# NeptuneSense_outdoor_station.net
KiCad netlist of a schematic drawn in Altium Designer
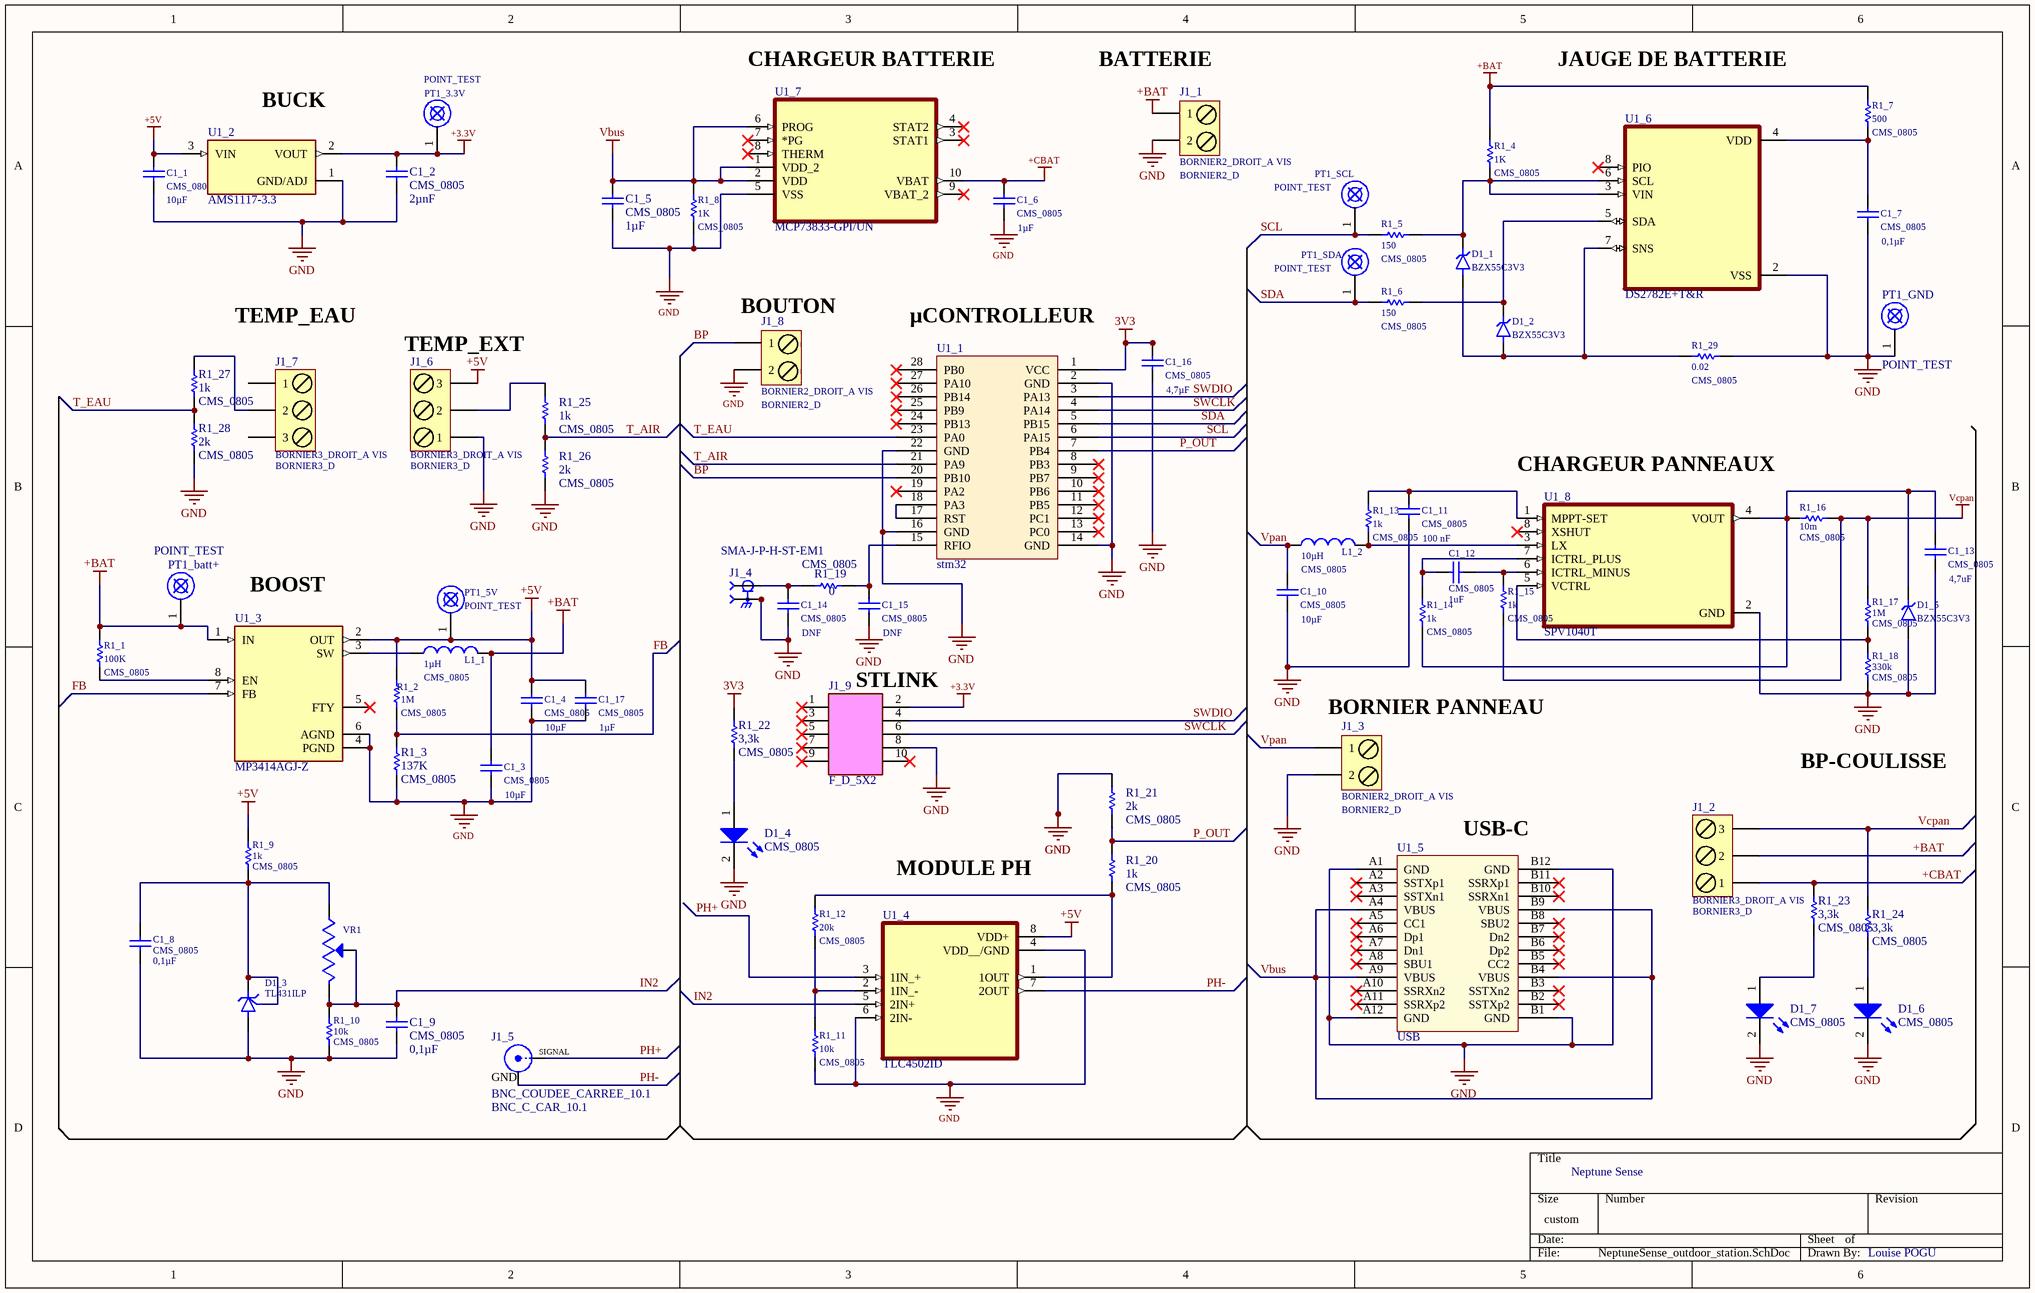
[diagram p0: NeptuneSense_outdoor_station.SchDoc]

(export (version "E")
  (design (tool "Eeschema 10.0.6"))
  (components
    (comp (ref "C1_1")
      (value "10µF")
      (footprint "CONDENSATEUR_CMS_0805")
      (description "CONDENSATEUR CMS CERAMIQUE 0805")
      (fields (field (name "TYPE") "CMS_0805") (field (name "Comment") "CMS_0805"))
      (libsource (lib "composants passifs") (part "CONDENSATEUR_CMS_CER_0805"))
    )
    (comp (ref "C1_2")
      (value "2µnF")
      (footprint "CONDENSATEUR_CMS_0805")
      (description "CONDENSATEUR CMS CERAMIQUE 0805")
      (fields (field (name "TYPE") "CMS_0805") (field (name "Comment") "CMS_0805"))
      (libsource (lib "composants passifs") (part "CONDENSATEUR_CMS_CER_0805"))
    )
    (comp (ref "C1_3")
      (value "10µF")
      (footprint "CONDENSATEUR_CMS_0805")
      (description "CONDENSATEUR CMS CERAMIQUE 0805")
      (fields (field (name "TYPE") "CMS_0805") (field (name "Comment") "CMS_0805"))
      (libsource (lib "composants passifs") (part "CONDENSATEUR_CMS_CER_0805"))
    )
    (comp (ref "C1_4")
      (value "10µF")
      (footprint "CONDENSATEUR_CMS_0805")
      (description "CONDENSATEUR CMS CERAMIQUE 0805")
      (fields (field (name "TYPE") "CMS_0805") (field (name "Comment") "CMS_0805"))
      (libsource (lib "composants passifs") (part "CONDENSATEUR_CMS_CER_0805"))
    )
    (comp (ref "C1_5")
      (value "1µF")
      (footprint "CONDENSATEUR_CMS_0805")
      (description "CONDENSATEUR CMS CERAMIQUE 0805")
      (fields (field (name "TYPE") "CMS_0805") (field (name "Comment") "CMS_0805"))
      (libsource (lib "composants passifs") (part "CONDENSATEUR_CMS_CER_0805"))
    )
    (comp (ref "C1_6")
      (value "1µF")
      (footprint "CONDENSATEUR_CMS_0805")
      (description "CONDENSATEUR CMS CERAMIQUE 0805")
      (fields (field (name "TYPE") "CMS_0805") (field (name "Comment") "CMS_0805"))
      (libsource (lib "composants passifs") (part "CONDENSATEUR_CMS_CER_0805"))
    )
    (comp (ref "C1_7")
      (value "0,1µF")
      (footprint "CONDENSATEUR_CMS_0805")
      (description "CONDENSATEUR CMS CERAMIQUE 0805")
      (fields (field (name "TYPE") "CMS_0805") (field (name "Comment") "CMS_0805"))
      (libsource (lib "composants passifs") (part "CONDENSATEUR_CMS_CER_0805"))
    )
    (comp (ref "C1_8")
      (value "0,1µF")
      (footprint "CONDENSATEUR_CMS_0805")
      (description "CONDENSATEUR CMS CERAMIQUE 0805")
      (fields (field (name "TYPE") "CMS_0805") (field (name "Comment") "CMS_0805"))
      (libsource (lib "composants passifs") (part "CONDENSATEUR_CMS_CER_0805"))
    )
    (comp (ref "C1_9")
      (value "0,1µF")
      (footprint "CONDENSATEUR_CMS_0805")
      (description "CONDENSATEUR CMS CERAMIQUE 0805")
      (fields (field (name "TYPE") "CMS_0805") (field (name "Comment") "CMS_0805"))
      (libsource (lib "composants passifs") (part "CONDENSATEUR_CMS_CER_0805"))
    )
    (comp (ref "C1_10")
      (value "10µF")
      (footprint "CONDENSATEUR_CMS_0805")
      (description "CONDENSATEUR CMS CERAMIQUE 0805")
      (fields (field (name "TYPE") "CMS_0805") (field (name "Comment") "CMS_0805"))
      (libsource (lib "composants passifs") (part "CONDENSATEUR_CMS_CER_0805"))
    )
    (comp (ref "C1_11")
      (value "100 nF")
      (footprint "CONDENSATEUR_CMS_0805")
      (description "CONDENSATEUR CMS CERAMIQUE 0805")
      (fields (field (name "TYPE") "CMS_0805") (field (name "Comment") "CMS_0805"))
      (libsource (lib "composants passifs") (part "CONDENSATEUR_CMS_CER_0805"))
    )
    (comp (ref "C1_12")
      (value "1uF")
      (footprint "CONDENSATEUR_CMS_0805")
      (description "CONDENSATEUR CMS CERAMIQUE 0805")
      (fields (field (name "TYPE") "CMS_0805") (field (name "Comment") "CMS_0805"))
      (libsource (lib "composants passifs") (part "CONDENSATEUR_CMS_CER_0805"))
    )
    (comp (ref "C1_13")
      (value "4,7uF")
      (footprint "CONDENSATEUR_CMS_0805")
      (description "CONDENSATEUR CMS CERAMIQUE 0805")
      (fields (field (name "TYPE") "CMS_0805") (field (name "Comment") "CMS_0805"))
      (libsource (lib "composants passifs") (part "CONDENSATEUR_CMS_CER_0805"))
    )
    (comp (ref "C1_14")
      (value "DNF")
      (footprint "CONDENSATEUR_CMS_0805")
      (description "CONDENSATEUR CMS CERAMIQUE 0805")
      (fields (field (name "TYPE") "CMS_0805") (field (name "Comment") "CMS_0805"))
      (libsource (lib "composants passifs") (part "CONDENSATEUR_CMS_CER_0805"))
    )
    (comp (ref "C1_15")
      (value "DNF")
      (footprint "CONDENSATEUR_CMS_0805")
      (description "CONDENSATEUR CMS CERAMIQUE 0805")
      (fields (field (name "TYPE") "CMS_0805") (field (name "Comment") "CMS_0805"))
      (libsource (lib "composants passifs") (part "CONDENSATEUR_CMS_CER_0805"))
    )
    (comp (ref "C1_16")
      (value "4,7µF")
      (footprint "CONDENSATEUR_CMS_0805")
      (description "CONDENSATEUR CMS CERAMIQUE 0805")
      (fields (field (name "TYPE") "CMS_0805") (field (name "Comment") "CMS_0805"))
      (libsource (lib "composants passifs") (part "CONDENSATEUR_CMS_CER_0805"))
    )
    (comp (ref "C1_17")
      (value "1µF")
      (footprint "CONDENSATEUR_CMS_0805")
      (description "CONDENSATEUR CMS CERAMIQUE 0805")
      (fields (field (name "TYPE") "CMS_0805") (field (name "Comment") "CMS_0805"))
      (libsource (lib "composants passifs") (part "CONDENSATEUR_CMS_CER_0805"))
    )
    (comp (ref "D1_1")
      (value "BZX55C3V3")
      (footprint "DIOAD928W47L399D179")
      (description "Zener Diode Single 3.3V 5% 85Ohm 500mW 2-Pin DO-35 T/R")
      (fields (field (name "MF") "Taiwan Semiconductor"))
      (libsource (lib "ESEO (Ecole Supérieure d'Electronique de l'Ouest)") (part "BZX55C3V3"))
    )
    (comp (ref "D1_2")
      (value "BZX55C3V3")
      (footprint "DIOAD928W47L399D179")
      (description "Zener Diode Single 3.3V 5% 85Ohm 500mW 2-Pin DO-35 T/R")
      (fields (field (name "MF") "Taiwan Semiconductor"))
      (libsource (lib "ESEO (Ecole Supérieure d'Electronique de l'Ouest)") (part "BZX55C3V3"))
    )
    (comp (ref "D1_3")
      (value "TL431ILP")
      (footprint "TO92127P520H660-3")
      (description "Ic, Tl431ilp, Tl431, Tl431a, Tl4 31b, Tl432, Tl432a, Tl432b<Nv")
      (libsource (lib "ESEO (Ecole Supérieure d'Electronique de l'Ouest)") (part "TL431ILP"))
    )
    (comp (ref "D1_4")
      (value "LED_CMS_0805")
      (footprint "LED_CMS_0805")
      (description "LED CMS 0805")
      (fields (field (name "TYPE") "CMS_0805"))
      (libsource (lib "affichage") (part "LED_CMS_0805"))
    )
    (comp (ref "D1_5")
      (value "BZX55C3V3")
      (footprint "DIOAD928W47L399D179")
      (description "Zener Diode Single 3.3V 5% 85Ohm 500mW 2-Pin DO-35 T/R")
      (fields (field (name "MF") "Taiwan Semiconductor"))
      (libsource (lib "ESEO (Ecole Supérieure d'Electronique de l'Ouest)") (part "BZX55C3V3"))
    )
    (comp (ref "D1_6")
      (value "LED_CMS_0805")
      (footprint "LED_CMS_0805")
      (description "LED CMS 0805")
      (fields (field (name "TYPE") "CMS_0805"))
      (libsource (lib "affichage") (part "LED_CMS_0805"))
    )
    (comp (ref "D1_7")
      (value "LED_CMS_0805")
      (footprint "LED_CMS_0805")
      (description "LED CMS 0805")
      (fields (field (name "TYPE") "CMS_0805"))
      (libsource (lib "affichage") (part "LED_CMS_0805"))
    )
    (comp (ref "J1_1")
      (value "BORNIER2_DROIT_A VIS")
      (footprint "BORNIER2_A_VIS")
      (description "BORNIER 2 PLOTS DROIT A VIS 5.08mm")
      (fields (field (name "TYPE") "BORNIER2_D") (field (name "SOURCE") "connecteurs.SchLib"))
      (libsource (lib "ESEO (Ecole Supérieure d'Electronique de l'Ouest)") (part "BORNIER2_DROIT_A VIS"))
    )
    (comp (ref "J1_2")
      (value "BORNIER3_DROIT_A VIS")
      (footprint "BORNIER3_A_VIS")
      (description "BORNIER 3 PLOTS DROIT A VIS 5.08mm")
      (fields (field (name "TYPE") "BORNIER3_D") (field (name "SOURCE") "connecteurs.SchLib"))
      (libsource (lib "ESEO (Ecole Supérieure d'Electronique de l'Ouest)") (part "BORNIER3_DROIT_A VIS"))
    )
    (comp (ref "J1_3")
      (value "BORNIER2_DROIT_A VIS")
      (footprint "BORNIER2_A_VIS")
      (description "BORNIER 2 PLOTS DROIT A VIS 5.08mm")
      (fields (field (name "TYPE") "BORNIER2_D") (field (name "SOURCE") "connecteurs.SchLib"))
      (libsource (lib "ESEO (Ecole Supérieure d'Electronique de l'Ouest)") (part "BORNIER2_DROIT_A VIS"))
    )
    (comp (ref "J1_4")
      (value "SMA-J-P-H-ST-EM1")
      (footprint "SAMTEC_SMA-J-P-H-ST-EM1")
      (description "SMA Connector Jack, Female Socket 50Ohm Board Edge, End Launch Solder")
      (fields (field (name "MF") "Samtec"))
      (libsource (lib "ESEO (Ecole Supérieure d'Electronique de l'Ouest)") (part "SMA-J-P-H-ST-EM1"))
    )
    (comp (ref "J1_5")
      (value "BNC_COUDEE_CARREE_10.1")
      (footprint "BNC_C_CAR_10.1")
      (description "EMBASE BNC COUDEE CARREE 50r - ESPACEMENT BROCHES GND=10.1")
      (fields (field (name "TYPE") "BNC_C_CAR_10.1") (field (name "SOURCE") "connecteurs.SchLib"))
      (libsource (lib "ESEO (Ecole Supérieure d'Electronique de l'Ouest)") (part "BNC_DROITE_CARREE_10.1"))
    )
    (comp (ref "J1_6")
      (value "BORNIER3_DROIT_A VIS")
      (footprint "BORNIER3_A_VIS")
      (description "BORNIER 3 PLOTS DROIT A VIS 5.08mm")
      (fields (field (name "TYPE") "BORNIER3_D") (field (name "SOURCE") "connecteurs.SchLib"))
      (libsource (lib "ESEO (Ecole Supérieure d'Electronique de l'Ouest)") (part "BORNIER3_DROIT_A VIS"))
    )
    (comp (ref "J1_7")
      (value "BORNIER3_DROIT_A VIS")
      (footprint "BORNIER3_A_VIS")
      (description "BORNIER 3 PLOTS DROIT A VIS 5.08mm")
      (fields (field (name "TYPE") "BORNIER3_D") (field (name "SOURCE") "connecteurs.SchLib"))
      (libsource (lib "") (part "BORNIER3_DROIT_A VIS_1"))
    )
    (comp (ref "J1_8")
      (value "BORNIER2_DROIT_A VIS")
      (footprint "BORNIER2_A_VIS")
      (description "BORNIER 2 PLOTS DROIT A VIS 5.08mm")
      (fields (field (name "TYPE") "BORNIER2_D") (field (name "SOURCE") "connecteurs.SchLib"))
      (libsource (lib "ESEO (Ecole Supérieure d'Electronique de l'Ouest)") (part "BORNIER2_DROIT_A VIS"))
    )
    (comp (ref "J1_9")
      (value "BARRETTE_5 CONTACTS_2 RANGEES_FEMELLE_DROITE")
      (footprint "BARRETTE_5X2_F_D")
      (description "BARRETTE 5 CONTACTS 2 RANGEES FEMELLE DROITE")
      (fields (field (name "TYPE") "F_D_5X2"))
      (libsource (lib "connecteurs") (part "BARRETTE_5 CONTACTS_2 RANGEES_FEMELLE_DROITE"))
    )
    (comp (ref "L1_1")
      (value "1µH")
      (footprint "INDUCTANCE_CMS_0805")
      (description "INDUCTANCE CMS 0805")
      (fields (field (name "TYPE") "CMS_0805") (field (name "Comment") "INDUCTANCE_CMS_0805"))
      (libsource (lib "composants passifs") (part "INDUCTANCE_CMS_0805"))
    )
    (comp (ref "L1_2")
      (value "10µH")
      (footprint "INDUCTANCE_CMS_0805")
      (description "INDUCTANCE CMS 0805")
      (fields (field (name "TYPE") "CMS_0805") (field (name "Comment") "INDUCTANCE_CMS_0805"))
      (libsource (lib "composants passifs") (part "INDUCTANCE_CMS_0805"))
    )
    (comp (ref "PT1_3.3V")
      (value "POINT_TEST")
      (footprint "POINT_TEST")
      (description "POINT TEST")
      (fields (field (name "SOURCE") "connecteurs.SchLib"))
      (libsource (lib "ESEO (Ecole Supérieure d'Electronique de l'Ouest)") (part "POINT_TEST"))
    )
    (comp (ref "PT1_5V")
      (value "POINT_TEST")
      (footprint "POINT_TEST")
      (description "POINT TEST")
      (fields (field (name "SOURCE") "connecteurs.SchLib"))
      (libsource (lib "ESEO (Ecole Supérieure d'Electronique de l'Ouest)") (part "POINT_TEST"))
    )
    (comp (ref "PT1_batt+")
      (value "POINT_TEST")
      (footprint "POINT_TEST")
      (description "POINT TEST")
      (fields (field (name "SOURCE") "connecteurs.SchLib"))
      (libsource (lib "ESEO (Ecole Supérieure d'Electronique de l'Ouest)") (part "POINT_TEST"))
    )
    (comp (ref "PT1_GND")
      (value "POINT_TEST")
      (footprint "POINT_TEST")
      (description "POINT TEST")
      (fields (field (name "SOURCE") "connecteurs.SchLib"))
      (libsource (lib "ESEO (Ecole Supérieure d'Electronique de l'Ouest)") (part "POINT_TEST"))
    )
    (comp (ref "PT1_SCL")
      (value "POINT_TEST")
      (footprint "POINT_TEST")
      (description "POINT TEST")
      (fields (field (name "SOURCE") "connecteurs.SchLib"))
      (libsource (lib "ESEO (Ecole Supérieure d'Electronique de l'Ouest)") (part "POINT_TEST"))
    )
    (comp (ref "PT1_SDA")
      (value "POINT_TEST")
      (footprint "POINT_TEST")
      (description "POINT TEST")
      (fields (field (name "SOURCE") "connecteurs.SchLib"))
      (libsource (lib "ESEO (Ecole Supérieure d'Electronique de l'Ouest)") (part "POINT_TEST"))
    )
    (comp (ref "R1_1")
      (value "100K")
      (footprint "RESISTANCE_CMS_0805")
      (description "RESISTANCE CMS 0805")
      (fields (field (name "TYPE") "CMS_0805") (field (name "Comment") "RESISTANCE_CMS_0805"))
      (libsource (lib "composants passifs") (part "RESISTANCE_CMS_0805"))
    )
    (comp (ref "R1_2")
      (value "1M")
      (footprint "RESISTANCE_CMS_0805")
      (description "RESISTANCE CMS 0805")
      (fields (field (name "TYPE") "CMS_0805") (field (name "Comment") "RESISTANCE_CMS_0805"))
      (libsource (lib "composants passifs") (part "RESISTANCE_CMS_0805"))
    )
    (comp (ref "R1_3")
      (value "137K")
      (footprint "RESISTANCE_CMS_0805")
      (description "RESISTANCE CMS 0805")
      (fields (field (name "TYPE") "CMS_0805") (field (name "Comment") "RESISTANCE_CMS_0805"))
      (libsource (lib "composants passifs") (part "RESISTANCE_CMS_0805"))
    )
    (comp (ref "R1_4")
      (value "1K")
      (footprint "RESISTANCE_CMS_0805")
      (description "RESISTANCE CMS 0805")
      (fields (field (name "TYPE") "CMS_0805") (field (name "Comment") "RESISTANCE_CMS_0805"))
      (libsource (lib "composants passifs") (part "RESISTANCE_CMS_0805"))
    )
    (comp (ref "R1_5")
      (value "150")
      (footprint "RESISTANCE_CMS_0805")
      (description "RESISTANCE CMS 0805")
      (fields (field (name "TYPE") "CMS_0805") (field (name "Comment") "RESISTANCE_CMS_0805"))
      (libsource (lib "composants passifs") (part "RESISTANCE_CMS_0805"))
    )
    (comp (ref "R1_6")
      (value "150")
      (footprint "RESISTANCE_CMS_0805")
      (description "RESISTANCE CMS 0805")
      (fields (field (name "TYPE") "CMS_0805") (field (name "Comment") "RESISTANCE_CMS_0805"))
      (libsource (lib "composants passifs") (part "RESISTANCE_CMS_0805"))
    )
    (comp (ref "R1_7")
      (value "500")
      (footprint "RESISTANCE_CMS_0805")
      (description "RESISTANCE CMS 0805")
      (fields (field (name "TYPE") "CMS_0805") (field (name "Comment") "RESISTANCE_CMS_0805"))
      (libsource (lib "composants passifs") (part "RESISTANCE_CMS_0805"))
    )
    (comp (ref "R1_8")
      (value "1K")
      (footprint "RESISTANCE_CMS_0805")
      (description "RESISTANCE CMS 0805")
      (fields (field (name "TYPE") "CMS_0805") (field (name "Comment") "RESISTANCE_CMS_0805"))
      (libsource (lib "composants passifs") (part "RESISTANCE_CMS_0805"))
    )
    (comp (ref "R1_9")
      (value "1k")
      (footprint "RESISTANCE_CMS_0805")
      (description "RESISTANCE CMS 0805")
      (fields (field (name "TYPE") "CMS_0805") (field (name "Comment") "RESISTANCE_CMS_0805"))
      (libsource (lib "composants passifs") (part "RESISTANCE_CMS_0805"))
    )
    (comp (ref "R1_10")
      (value "10k")
      (footprint "RESISTANCE_CMS_0805")
      (description "RESISTANCE CMS 0805")
      (fields (field (name "TYPE") "CMS_0805") (field (name "Comment") "RESISTANCE_CMS_0805"))
      (libsource (lib "composants passifs") (part "RESISTANCE_CMS_0805"))
    )
    (comp (ref "R1_11")
      (value "10k")
      (footprint "RESISTANCE_CMS_0805")
      (description "RESISTANCE CMS 0805")
      (fields (field (name "TYPE") "CMS_0805") (field (name "Comment") "RESISTANCE_CMS_0805"))
      (libsource (lib "composants passifs") (part "RESISTANCE_CMS_0805"))
    )
    (comp (ref "R1_12")
      (value "20k")
      (footprint "RESISTANCE_CMS_0805")
      (description "RESISTANCE CMS 0805")
      (fields (field (name "TYPE") "CMS_0805") (field (name "Comment") "RESISTANCE_CMS_0805"))
      (libsource (lib "composants passifs") (part "RESISTANCE_CMS_0805"))
    )
    (comp (ref "R1_13")
      (value "1k")
      (footprint "RESISTANCE_CMS_0805")
      (description "RESISTANCE CMS 0805")
      (fields (field (name "TYPE") "CMS_0805") (field (name "Comment") "RESISTANCE_CMS_0805"))
      (libsource (lib "composants passifs") (part "RESISTANCE_CMS_0805"))
    )
    (comp (ref "R1_14")
      (value "1k")
      (footprint "RESISTANCE_CMS_0805")
      (description "RESISTANCE CMS 0805")
      (fields (field (name "TYPE") "CMS_0805") (field (name "Comment") "RESISTANCE_CMS_0805"))
      (libsource (lib "composants passifs") (part "RESISTANCE_CMS_0805"))
    )
    (comp (ref "R1_15")
      (value "1k")
      (footprint "RESISTANCE_CMS_0805")
      (description "RESISTANCE CMS 0805")
      (fields (field (name "TYPE") "CMS_0805") (field (name "Comment") "RESISTANCE_CMS_0805"))
      (libsource (lib "composants passifs") (part "RESISTANCE_CMS_0805"))
    )
    (comp (ref "R1_16")
      (value "10m")
      (footprint "RESISTANCE_CMS_0805")
      (description "RESISTANCE CMS 0805")
      (fields (field (name "TYPE") "CMS_0805") (field (name "Comment") "RESISTANCE_CMS_0805"))
      (libsource (lib "composants passifs") (part "RESISTANCE_CMS_0805"))
    )
    (comp (ref "R1_17")
      (value "1M")
      (footprint "RESISTANCE_CMS_0805")
      (description "RESISTANCE CMS 0805")
      (fields (field (name "TYPE") "CMS_0805") (field (name "Comment") "RESISTANCE_CMS_0805"))
      (libsource (lib "composants passifs") (part "RESISTANCE_CMS_0805"))
    )
    (comp (ref "R1_18")
      (value "330k")
      (footprint "RESISTANCE_CMS_0805")
      (description "RESISTANCE CMS 0805")
      (fields (field (name "TYPE") "CMS_0805") (field (name "Comment") "RESISTANCE_CMS_0805"))
      (libsource (lib "composants passifs") (part "RESISTANCE_CMS_0805"))
    )
    (comp (ref "R1_19")
      (value "0")
      (footprint "RESISTANCE_CMS_0805")
      (description "RESISTANCE CMS 0805")
      (fields (field (name "TYPE") "CMS_0805") (field (name "Comment") "RESISTANCE_CMS_0805"))
      (libsource (lib "composants passifs") (part "RESISTANCE_CMS_0805"))
    )
    (comp (ref "R1_20")
      (value "1k")
      (footprint "RESISTANCE_CMS_0805")
      (description "RESISTANCE CMS 0805")
      (fields (field (name "TYPE") "CMS_0805") (field (name "Comment") "RESISTANCE_CMS_0805"))
      (libsource (lib "composants passifs") (part "RESISTANCE_CMS_0805"))
    )
    (comp (ref "R1_21")
      (value "2k")
      (footprint "RESISTANCE_CMS_0805")
      (description "RESISTANCE CMS 0805")
      (fields (field (name "TYPE") "CMS_0805") (field (name "Comment") "RESISTANCE_CMS_0805"))
      (libsource (lib "composants passifs") (part "RESISTANCE_CMS_0805"))
    )
    (comp (ref "R1_22")
      (value "3,3k")
      (footprint "RESISTANCE_CMS_0805")
      (description "RESISTANCE CMS 0805")
      (fields (field (name "TYPE") "CMS_0805") (field (name "Comment") "RESISTANCE_CMS_0805"))
      (libsource (lib "composants passifs") (part "RESISTANCE_CMS_0805"))
    )
    (comp (ref "R1_23")
      (value "3,3k")
      (footprint "RESISTANCE_CMS_0805")
      (description "RESISTANCE CMS 0805")
      (fields (field (name "TYPE") "CMS_0805") (field (name "Comment") "RESISTANCE_CMS_0805"))
      (libsource (lib "composants passifs") (part "RESISTANCE_CMS_0805"))
    )
    (comp (ref "R1_24")
      (value "3,3k")
      (footprint "RESISTANCE_CMS_0805")
      (description "RESISTANCE CMS 0805")
      (fields (field (name "TYPE") "CMS_0805") (field (name "Comment") "RESISTANCE_CMS_0805"))
      (libsource (lib "composants passifs") (part "RESISTANCE_CMS_0805"))
    )
    (comp (ref "R1_25")
      (value "1k")
      (footprint "RESISTANCE_CMS_0805")
      (description "RESISTANCE CMS 0805")
      (fields (field (name "TYPE") "CMS_0805") (field (name "Comment") "RESISTANCE_CMS_0805"))
      (libsource (lib "composants passifs") (part "RESISTANCE_CMS_0805"))
    )
    (comp (ref "R1_26")
      (value "2k")
      (footprint "RESISTANCE_CMS_0805")
      (description "RESISTANCE CMS 0805")
      (fields (field (name "TYPE") "CMS_0805") (field (name "Comment") "RESISTANCE_CMS_0805"))
      (libsource (lib "composants passifs") (part "RESISTANCE_CMS_0805"))
    )
    (comp (ref "R1_27")
      (value "1k")
      (footprint "RESISTANCE_CMS_0805")
      (description "RESISTANCE CMS 0805")
      (fields (field (name "TYPE") "CMS_0805") (field (name "Comment") "RESISTANCE_CMS_0805"))
      (libsource (lib "composants passifs") (part "RESISTANCE_CMS_0805"))
    )
    (comp (ref "R1_28")
      (value "2k")
      (footprint "RESISTANCE_CMS_0805")
      (description "RESISTANCE CMS 0805")
      (fields (field (name "TYPE") "CMS_0805") (field (name "Comment") "RESISTANCE_CMS_0805"))
      (libsource (lib "composants passifs") (part "RESISTANCE_CMS_0805"))
    )
    (comp (ref "R1_29")
      (value "0.02")
      (footprint "RESISTANCE_CMS_0805")
      (description "RESISTANCE CMS 0805")
      (fields (field (name "TYPE") "CMS_0805") (field (name "Comment") "RESISTANCE_CMS_0805"))
      (libsource (lib "composants passifs") (part "RESISTANCE_CMS_0805"))
    )
    (comp (ref "U1_1") (value "stm32") (footprint "QFN127P600-8N") (libsource (lib "Schlib1") (part "stm32")))
    (comp (ref "U1_2")
      (value "AMS1117-3.3")
      (footprint "SOT229P700X180-4N")
      (description "LDO Voltage Regulators 800MA LDO LINEAR REG")
      (fields (field (name "MF") "ams AG"))
      (libsource (lib "ESEO (Ecole Supérieure d'Electronique de l'Ouest)") (part "AMS1117-3.3"))
    )
    (comp (ref "U1_3")
      (value "MP3414AGJ-Z")
      (footprint "SOT65P280X100-8N")
      (description "Boost Switching Regulator IC Positive Adjustable 2V 1 Output 3A SOT-23-8")
      (fields (field (name "MF") "Monolithic Power"))
      (libsource (lib "ESEO (Ecole Supérieure d'Electronique de l'Ouest)") (part "MP3414AGJ-Z"))
    )
    (comp (ref "U1_4")
      (value "TLC4502ID")
      (footprint "SOIC127P599X175-8N")
      (description "Advanced LinEPIC Self-Calibrating Precision Dual Operational Amplifier 8-SOIC -40 to 125")
      (fields (field (name "MF") "Texas Instruments"))
      (libsource (lib "ESEO (Ecole Supérieure d'Electronique de l'Ouest)") (part "TLC4502ID"))
    )
    (comp (ref "U1_5") (value "USB") (footprint "USB") (libsource (lib "Schlib1") (part "USB")))
    (comp (ref "U1_6")
      (value "DS2782E+T&R")
      (footprint "SOP65P640X110-8N")
      (description "Power Management IC Development Tools DS2782 EVAL KIT")
      (fields (field (name "MP") "DS2782E+T") (field (name "MF") "Maxim Integrated"))
      (libsource (lib "ESEO (Ecole Supérieure d'Electronique de l'Ouest)") (part "DS2782E+T&R"))
    )
    (comp (ref "U1_7")
      (value "MCP73833-GPI/UN")
      (footprint "SOP50P490X110-10N")
      (description "Charger IC Lithium Ion/Polymer 10-MSOP")
      (fields (field (name "MF") "Microchip") (field (name "DIGI-KEY_PART_NUMBER") "MCP73833-GPI/UN-ND"))
      (libsource (lib "ESEO (Ecole Supérieure d'Electronique de l'Ouest)") (part "MCP73833-GPI/UN"))
    )
    (comp (ref "U1_8")
      (value "SPV1040T")
      (footprint "SOP65P640X120-8N")
      (description "IC BATTERY CHARGER SOLAR 8TSSOP")
      (fields (field (name "MF") "STMicroelectronics"))
      (libsource (lib "ESEO (Ecole Supérieure d'Electronique de l'Ouest)") (part "SPV1040T"))
    )
    (comp (ref "VR1")
      (value "3296W1103LF")
      (footprint "TRIM_3296W1103LF")
      (description "Trimmer, Potentiometer 10kohm 25turn Thd")
      (fields (field (name "MF") "Bourns"))
      (libsource (lib "ESEO (Ecole Supérieure d'Electronique de l'Ouest)") (part "3296W1103LF"))
    )
  )
  (nets
    (net (code "1") (name "+3.3V") (class "Default")
      (node (ref "C1_2") (pin "2") (pinfunction "2_2") (pintype "passive"))
      (node (ref "J1_9") (pin "2") (pinfunction "2_2") (pintype "passive"))
      (node (ref "PT1_3.3V") (pin "1") (pinfunction "3_1") (pintype "passive"))
      (node (ref "U1_2") (pin "2") (pinfunction "VOUT_2") (pintype "output"))
    )
    (net (code "2") (name "+5V") (class "Default")
      (node (ref "C1_1") (pin "1") (pinfunction "1_1") (pintype "passive"))
      (node (ref "C1_17") (pin "2") (pinfunction "2_2") (pintype "passive"))
      (node (ref "C1_4") (pin "2") (pinfunction "2_2") (pintype "passive"))
      (node (ref "J1_6") (pin "3") (pinfunction "3_3") (pintype "passive"))
      (node (ref "PT1_5V") (pin "1") (pinfunction "3_1") (pintype "passive"))
      (node (ref "R1_2") (pin "2") (pinfunction "2_2") (pintype "passive"))
      (node (ref "R1_9") (pin "1") (pinfunction "1_1") (pintype "passive"))
      (node (ref "U1_2") (pin "3") (pinfunction "VIN_3") (pintype "input"))
      (node (ref "U1_3") (pin "2") (pinfunction "OUT_2") (pintype "output"))
      (node (ref "U1_4") (pin "8") (pinfunction "VDD+_8") (pintype "power_in"))
    )
    (net (code "3") (name "+BAT") (class "Default")
      (node (ref "C1_3") (pin "2") (pinfunction "2_2") (pintype "passive"))
      (node (ref "J1_1") (pin "1") (pinfunction "1_1") (pintype "passive"))
      (node (ref "J1_2") (pin "2") (pinfunction "2_2") (pintype "passive"))
      (node (ref "L1_1") (pin "2") (pinfunction "2_2") (pintype "passive"))
      (node (ref "PT1_batt+") (pin "1") (pinfunction "3_1") (pintype "passive"))
      (node (ref "R1_1") (pin "2") (pinfunction "2_2") (pintype "passive"))
      (node (ref "R1_4") (pin "2") (pinfunction "2_2") (pintype "passive"))
      (node (ref "R1_7") (pin "2") (pinfunction "2_2") (pintype "passive"))
      (node (ref "U1_3") (pin "1") (pinfunction "IN_1") (pintype "input"))
    )
    (net (code "4") (name "+CBAT") (class "Default")
      (node (ref "C1_6") (pin "2") (pinfunction "2_2") (pintype "passive"))
      (node (ref "J1_2") (pin "1") (pinfunction "1_1") (pintype "passive"))
      (node (ref "R1_23") (pin "1") (pinfunction "1_1") (pintype "passive"))
      (node (ref "U1_7") (pin "10") (pinfunction "VBAT_10") (pintype "output"))
    )
    (net (code "5") (name "/BP") (class "Default")
      (node (ref "J1_8") (pin "1") (pinfunction "1_1") (pintype "passive"))
      (node (ref "U1_1") (pin "20") (pinfunction "PB10_20") (pintype "passive"))
    )
    (net (code "6") (name "/FB") (class "Default")
      (node (ref "R1_2") (pin "1") (pinfunction "1_1") (pintype "passive"))
      (node (ref "R1_3") (pin "2") (pinfunction "2_2") (pintype "passive"))
      (node (ref "U1_3") (pin "7") (pinfunction "FB_7") (pintype "input"))
    )
    (net (code "7") (name "/IN2") (class "Default")
      (node (ref "C1_9") (pin "2") (pinfunction "2_2") (pintype "passive"))
      (node (ref "R1_10") (pin "1") (pinfunction "1_1") (pintype "passive"))
      (node (ref "U1_4") (pin "5") (pinfunction "2IN+_5") (pintype "input"))
      (node (ref "VR1") (pin "2") (pinfunction "WIPER_2") (pintype "passive"))
      (node (ref "VR1") (pin "3") (pinfunction "CW_3") (pintype "passive"))
    )
    (net (code "8") (name "/PH+") (class "Default")
      (node (ref "J1_5") (pin "1") (pinfunction "X_1") (pintype "passive"))
      (node (ref "U1_4") (pin "3") (pinfunction "1IN_+_3") (pintype "input"))
    )
    (net (code "9") (name "/PH-") (class "Default")
      (node (ref "J1_5") (pin "2") (pinfunction "Y_2") (pintype "passive"))
      (node (ref "U1_4") (pin "7") (pinfunction "2OUT_7") (pintype "output"))
    )
    (net (code "10") (name "/P_OUT") (class "Default")
      (node (ref "R1_20") (pin "1") (pinfunction "1_1") (pintype "passive"))
      (node (ref "R1_21") (pin "2") (pinfunction "2_2") (pintype "passive"))
      (node (ref "U1_1") (pin "7") (pinfunction "PB4_7") (pintype "passive"))
    )
    (net (code "11") (name "/SCL") (class "Default")
      (node (ref "PT1_SCL") (pin "1") (pinfunction "3_1") (pintype "passive"))
      (node (ref "R1_5") (pin "2") (pinfunction "2_2") (pintype "passive"))
      (node (ref "U1_1") (pin "6") (pinfunction "PA15_6") (pintype "passive"))
    )
    (net (code "12") (name "/SDA") (class "Default")
      (node (ref "PT1_SDA") (pin "1") (pinfunction "3_1") (pintype "passive"))
      (node (ref "R1_6") (pin "2") (pinfunction "2_2") (pintype "passive"))
      (node (ref "U1_1") (pin "5") (pinfunction "PB15_5") (pintype "passive"))
    )
    (net (code "13") (name "/SWCLK") (class "Default")
      (node (ref "J1_9") (pin "6") (pinfunction "6_6") (pintype "passive"))
      (node (ref "U1_1") (pin "4") (pinfunction "PA14_4") (pintype "passive"))
    )
    (net (code "14") (name "/SWDIO") (class "Default")
      (node (ref "J1_9") (pin "4") (pinfunction "4_4") (pintype "passive"))
      (node (ref "U1_1") (pin "3") (pinfunction "PA13_3") (pintype "passive"))
    )
    (net (code "15") (name "/T_AIR") (class "Default")
      (node (ref "R1_25") (pin "2") (pinfunction "2_2") (pintype "passive"))
      (node (ref "R1_26") (pin "1") (pinfunction "1_1") (pintype "passive"))
      (node (ref "U1_1") (pin "21") (pinfunction "PA9_21") (pintype "passive"))
    )
    (net (code "16") (name "/T_EAU") (class "Default")
      (node (ref "R1_27") (pin "2") (pinfunction "2_2") (pintype "passive"))
      (node (ref "R1_28") (pin "1") (pinfunction "1_1") (pintype "passive"))
      (node (ref "U1_1") (pin "23") (pinfunction "PA0_23") (pintype "passive"))
    )
    (net (code "17") (name "/Vpan") (class "Default")
      (node (ref "C1_10") (pin "2") (pinfunction "2_2") (pintype "passive"))
      (node (ref "J1_3") (pin "1") (pinfunction "1_1") (pintype "passive"))
      (node (ref "L1_2") (pin "1") (pinfunction "1_1") (pintype "passive"))
    )
    (net (code "18") (name "3V3") (class "Default")
      (node (ref "C1_16") (pin "2") (pinfunction "2_2") (pintype "passive"))
      (node (ref "R1_22") (pin "1") (pinfunction "1_1") (pintype "passive"))
      (node (ref "U1_1") (pin "1") (pinfunction "VCC_1") (pintype "passive"))
    )
    (net (code "19") (name "GND") (class "Default")
      (node (ref "C1_1") (pin "2") (pinfunction "2_2") (pintype "passive"))
      (node (ref "C1_10") (pin "1") (pinfunction "1_1") (pintype "passive"))
      (node (ref "C1_11") (pin "1") (pinfunction "1_1") (pintype "passive"))
      (node (ref "C1_13") (pin "1") (pinfunction "1_1") (pintype "passive"))
      (node (ref "C1_14") (pin "1") (pinfunction "1_1") (pintype "passive"))
      (node (ref "C1_15") (pin "1") (pinfunction "1_1") (pintype "passive"))
      (node (ref "C1_16") (pin "1") (pinfunction "1_1") (pintype "passive"))
      (node (ref "C1_17") (pin "1") (pinfunction "1_1") (pintype "passive"))
      (node (ref "C1_2") (pin "1") (pinfunction "1_1") (pintype "passive"))
      (node (ref "C1_3") (pin "1") (pinfunction "1_1") (pintype "passive"))
      (node (ref "C1_4") (pin "1") (pinfunction "1_1") (pintype "passive"))
      (node (ref "C1_5") (pin "1") (pinfunction "1_1") (pintype "passive"))
      (node (ref "C1_6") (pin "1") (pinfunction "1_1") (pintype "passive"))
      (node (ref "C1_7") (pin "1") (pinfunction "1_1") (pintype "passive"))
      (node (ref "C1_8") (pin "1") (pinfunction "1_1") (pintype "passive"))
      (node (ref "C1_9") (pin "1") (pinfunction "1_1") (pintype "passive"))
      (node (ref "D1_3") (pin "2") (pinfunction "A_2") (pintype "passive"))
      (node (ref "D1_4") (pin "2") (pinfunction "2_2") (pintype "passive"))
      (node (ref "D1_5") (pin "A") (pinfunction "A_A") (pintype "passive"))
      (node (ref "D1_6") (pin "2") (pinfunction "2_2") (pintype "passive"))
      (node (ref "D1_7") (pin "2") (pinfunction "2_2") (pintype "passive"))
      (node (ref "J1_1") (pin "2") (pinfunction "2_2") (pintype "passive"))
      (node (ref "J1_3") (pin "2") (pinfunction "2_2") (pintype "passive"))
      (node (ref "J1_4") (pin "2_1") (pinfunction "2_2_1") (pintype "passive"))
      (node (ref "J1_4") (pin "2_2") (pinfunction "2_2_2") (pintype "passive"))
      (node (ref "J1_4") (pin "3_1") (pinfunction "2_3_1") (pintype "passive"))
      (node (ref "J1_4") (pin "3_2") (pinfunction "2_3_2") (pintype "passive"))
      (node (ref "J1_6") (pin "1") (pinfunction "1_1") (pintype "passive"))
      (node (ref "J1_8") (pin "2") (pinfunction "2_2") (pintype "passive"))
      (node (ref "J1_9") (pin "8") (pinfunction "8_8") (pintype "passive"))
      (node (ref "PT1_GND") (pin "1") (pinfunction "3_1") (pintype "passive"))
      (node (ref "R1_10") (pin "2") (pinfunction "2_2") (pintype "passive"))
      (node (ref "R1_11") (pin "2") (pinfunction "2_2") (pintype "passive"))
      (node (ref "R1_18") (pin "1") (pinfunction "1_1") (pintype "passive"))
      (node (ref "R1_21") (pin "1") (pinfunction "1_1") (pintype "passive"))
      (node (ref "R1_26") (pin "2") (pinfunction "2_2") (pintype "passive"))
      (node (ref "R1_28") (pin "2") (pinfunction "2_2") (pintype "passive"))
      (node (ref "R1_29") (pin "1") (pinfunction "1_1") (pintype "passive"))
      (node (ref "R1_3") (pin "1") (pinfunction "1_1") (pintype "passive"))
      (node (ref "R1_8") (pin "1") (pinfunction "1_1") (pintype "passive"))
      (node (ref "U1_1") (pin "14") (pinfunction "GND_14") (pintype "passive"))
      (node (ref "U1_1") (pin "16") (pinfunction "GND_16") (pintype "passive"))
      (node (ref "U1_1") (pin "2") (pinfunction "GND_2") (pintype "passive"))
      (node (ref "U1_1") (pin "22") (pinfunction "GND_22") (pintype "passive"))
      (node (ref "U1_2") (pin "1") (pinfunction "GND/ADJ_1") (pintype "power_in"))
      (node (ref "U1_3") (pin "4") (pinfunction "PGND_4") (pintype "power_in"))
      (node (ref "U1_3") (pin "6") (pinfunction "AGND_6") (pintype "power_in"))
      (node (ref "U1_4") (pin "4") (pinfunction "VDD__/GND_4") (pintype "power_in"))
      (node (ref "U1_4") (pin "6") (pinfunction "2IN-_6") (pintype "input"))
      (node (ref "U1_5") (pin "A1") (pinfunction "GND_A1") (pintype "passive"))
      (node (ref "U1_5") (pin "A12") (pinfunction "GND_A12") (pintype "passive"))
      (node (ref "U1_5") (pin "B1") (pinfunction "GND_B1") (pintype "passive"))
      (node (ref "U1_5") (pin "B12") (pinfunction "GND_B12") (pintype "passive"))
      (node (ref "U1_6") (pin "2") (pinfunction "VSS_2") (pintype "power_in"))
      (node (ref "U1_7") (pin "5") (pinfunction "VSS_5") (pintype "passive"))
      (node (ref "U1_8") (pin "2") (pinfunction "GND_2") (pintype "power_in"))
    )
    (net (code "20") (name "Net-(C1_14-Pad2)") (class "Default")
      (node (ref "C1_14") (pin "2") (pinfunction "2_2") (pintype "passive"))
      (node (ref "J1_4") (pin "1") (pinfunction "1_1") (pintype "passive"))
      (node (ref "R1_19") (pin "2") (pinfunction "2_2") (pintype "passive"))
    )
    (net (code "21") (name "Net-(D1_1-K)") (class "Default")
      (node (ref "D1_1") (pin "C") (pinfunction "K_C") (pintype "passive"))
      (node (ref "R1_4") (pin "1") (pinfunction "1_1") (pintype "passive"))
      (node (ref "R1_5") (pin "1") (pinfunction "1_1") (pintype "passive"))
      (node (ref "U1_6") (pin "3") (pinfunction "VIN_3") (pintype "input"))
      (node (ref "U1_6") (pin "6") (pinfunction "SCL_6") (pintype "input"))
    )
    (net (code "22") (name "Net-(D1_2-K)") (class "Default")
      (node (ref "D1_2") (pin "C") (pinfunction "K_C") (pintype "passive"))
      (node (ref "R1_6") (pin "1") (pinfunction "1_1") (pintype "passive"))
      (node (ref "U1_6") (pin "5") (pinfunction "SDA_5") (pintype "bidirectional"))
    )
    (net (code "23") (name "Net-(D1_3-C)") (class "Default")
      (node (ref "C1_8") (pin "2") (pinfunction "2_2") (pintype "passive"))
      (node (ref "D1_3") (pin "1") (pinfunction "REF_1") (pintype "passive"))
      (node (ref "D1_3") (pin "3") (pinfunction "C_3") (pintype "passive"))
      (node (ref "R1_9") (pin "2") (pinfunction "2_2") (pintype "passive"))
      (node (ref "VR1") (pin "1") (pinfunction "CCW_1") (pintype "passive"))
    )
    (net (code "24") (name "Net-(D1_4-Pad1)") (class "Default")
      (node (ref "D1_4") (pin "1") (pinfunction "1_1") (pintype "passive"))
      (node (ref "R1_22") (pin "2") (pinfunction "2_2") (pintype "passive"))
    )
    (net (code "25") (name "Net-(D1_5-K)") (class "Default")
      (node (ref "C1_13") (pin "2") (pinfunction "2_2") (pintype "passive"))
      (node (ref "D1_5") (pin "C") (pinfunction "K_C") (pintype "passive"))
      (node (ref "R1_14") (pin "2") (pinfunction "2_2") (pintype "passive"))
      (node (ref "R1_16") (pin "1") (pinfunction "1_1") (pintype "passive"))
      (node (ref "U1_8") (pin "4") (pinfunction "VOUT_4") (pintype "output"))
    )
    (net (code "26") (name "Net-(D1_6-Pad1)") (class "Default")
      (node (ref "D1_6") (pin "1") (pinfunction "1_1") (pintype "passive"))
      (node (ref "R1_24") (pin "2") (pinfunction "2_2") (pintype "passive"))
    )
    (net (code "27") (name "Net-(D1_7-Pad1)") (class "Default")
      (node (ref "D1_7") (pin "1") (pinfunction "1_1") (pintype "passive"))
      (node (ref "R1_23") (pin "2") (pinfunction "2_2") (pintype "passive"))
    )
    (net (code "28") (name "Net-(J1_6-Pad2)") (class "Default")
      (node (ref "J1_6") (pin "2") (pinfunction "2_2") (pintype "passive"))
      (node (ref "R1_25") (pin "1") (pinfunction "1_1") (pintype "passive"))
    )
    (net (code "29") (name "Net-(J1_7-Pad2)") (class "Default")
      (node (ref "J1_7") (pin "2") (pinfunction "2_2") (pintype "passive"))
      (node (ref "R1_27") (pin "1") (pinfunction "1_1") (pintype "passive"))
    )
    (net (code "30") (name "Net-(U1_1-PA3)") (class "Default")
      (node (ref "U1_1") (pin "17") (pinfunction "RST_17") (pintype "passive"))
      (node (ref "U1_1") (pin "18") (pinfunction "PA3_18") (pintype "passive"))
    )
    (net (code "31") (name "Net-(U1_1-RFIO)") (class "Default")
      (node (ref "C1_15") (pin "2") (pinfunction "2_2") (pintype "passive"))
      (node (ref "R1_19") (pin "1") (pinfunction "1_1") (pintype "passive"))
      (node (ref "U1_1") (pin "15") (pinfunction "RFIO_15") (pintype "passive"))
    )
    (net (code "32") (name "Net-(U1_3-EN)") (class "Default")
      (node (ref "R1_1") (pin "1") (pinfunction "1_1") (pintype "passive"))
      (node (ref "U1_3") (pin "8") (pinfunction "EN_8") (pintype "input"))
    )
    (net (code "33") (name "Net-(U1_3-SW)") (class "Default")
      (node (ref "L1_1") (pin "1") (pinfunction "1_1") (pintype "passive"))
      (node (ref "U1_3") (pin "3") (pinfunction "SW_3") (pintype "output"))
    )
    (net (code "34") (name "Net-(U1_4-1IN_-)") (class "Default")
      (node (ref "R1_11") (pin "1") (pinfunction "1_1") (pintype "passive"))
      (node (ref "R1_12") (pin "2") (pinfunction "2_2") (pintype "passive"))
      (node (ref "U1_4") (pin "2") (pinfunction "1IN_-_2") (pintype "input"))
    )
    (net (code "35") (name "Net-(U1_4-1OUT)") (class "Default")
      (node (ref "R1_12") (pin "1") (pinfunction "1_1") (pintype "passive"))
      (node (ref "R1_20") (pin "2") (pinfunction "2_2") (pintype "passive"))
      (node (ref "U1_4") (pin "1") (pinfunction "1OUT_1") (pintype "output"))
    )
    (net (code "36") (name "Net-(U1_6-SNS)") (class "Default")
      (node (ref "D1_1") (pin "A") (pinfunction "A_A") (pintype "passive"))
      (node (ref "D1_2") (pin "A") (pinfunction "A_A") (pintype "passive"))
      (node (ref "R1_29") (pin "2") (pinfunction "2_2") (pintype "passive"))
      (node (ref "U1_6") (pin "7") (pinfunction "SNS_7") (pintype "bidirectional"))
    )
    (net (code "37") (name "Net-(U1_6-VDD)") (class "Default")
      (node (ref "C1_7") (pin "2") (pinfunction "2_2") (pintype "passive"))
      (node (ref "R1_7") (pin "1") (pinfunction "1_1") (pintype "passive"))
      (node (ref "U1_6") (pin "4") (pinfunction "VDD_4") (pintype "power_in"))
    )
    (net (code "38") (name "Net-(U1_8-ICTRL_MINUS)") (class "Default")
      (node (ref "C1_12") (pin "1") (pinfunction "1_1") (pintype "passive"))
      (node (ref "R1_15") (pin "1") (pinfunction "1_1") (pintype "passive"))
      (node (ref "U1_8") (pin "6") (pinfunction "ICTRL_MINUS_6") (pintype "input"))
    )
    (net (code "39") (name "Net-(U1_8-ICTRL_PLUS)") (class "Default")
      (node (ref "C1_12") (pin "2") (pinfunction "2_2") (pintype "passive"))
      (node (ref "R1_14") (pin "1") (pinfunction "1_1") (pintype "passive"))
      (node (ref "U1_8") (pin "7") (pinfunction "ICTRL_PLUS_7") (pintype "input"))
    )
    (net (code "40") (name "Net-(U1_8-LX)") (class "Default")
      (node (ref "L1_2") (pin "2") (pinfunction "2_2") (pintype "passive"))
      (node (ref "R1_13") (pin "2") (pinfunction "2_2") (pintype "passive"))
      (node (ref "U1_8") (pin "3") (pinfunction "LX_3") (pintype "input"))
    )
    (net (code "41") (name "Net-(U1_8-MPPT-SET)") (class "Default")
      (node (ref "C1_11") (pin "2") (pinfunction "2_2") (pintype "passive"))
      (node (ref "R1_13") (pin "1") (pinfunction "1_1") (pintype "passive"))
      (node (ref "U1_8") (pin "1") (pinfunction "MPPT-SET_1") (pintype "input"))
    )
    (net (code "42") (name "Net-(U1_8-VCTRL)") (class "Default")
      (node (ref "R1_17") (pin "1") (pinfunction "1_1") (pintype "passive"))
      (node (ref "R1_18") (pin "2") (pinfunction "2_2") (pintype "passive"))
      (node (ref "U1_8") (pin "5") (pinfunction "VCTRL_5") (pintype "input"))
    )
    (net (code "43") (name "Vbus") (class "Default")
      (node (ref "C1_5") (pin "2") (pinfunction "2_2") (pintype "passive"))
      (node (ref "R1_8") (pin "2") (pinfunction "2_2") (pintype "passive"))
      (node (ref "U1_5") (pin "A4") (pinfunction "VBUS_A4") (pintype "passive"))
      (node (ref "U1_5") (pin "A9") (pinfunction "VBUS_A9") (pintype "passive"))
      (node (ref "U1_5") (pin "B4") (pinfunction "VBUS_B4") (pintype "passive"))
      (node (ref "U1_5") (pin "B9") (pinfunction "VBUS_B9") (pintype "passive"))
      (node (ref "U1_7") (pin "1") (pinfunction "VDD_2_1") (pintype "power_in"))
      (node (ref "U1_7") (pin "2") (pinfunction "VDD_2") (pintype "power_in"))
      (node (ref "U1_7") (pin "6") (pinfunction "PROG_6") (pintype "input"))
    )
    (net (code "44") (name "Vcpan") (class "Default")
      (node (ref "J1_2") (pin "3") (pinfunction "3_3") (pintype "passive"))
      (node (ref "R1_15") (pin "2") (pinfunction "2_2") (pintype "passive"))
      (node (ref "R1_16") (pin "2") (pinfunction "2_2") (pintype "passive"))
      (node (ref "R1_17") (pin "2") (pinfunction "2_2") (pintype "passive"))
      (node (ref "R1_24") (pin "1") (pinfunction "1_1") (pintype "passive"))
    )
    (net (code "45") (name "unconnected-(J1_7-Pad1)") (class "Default")
      (node (ref "J1_7") (pin "1") (pinfunction "1_1") (pintype "passive"))
    )
    (net (code "46") (name "unconnected-(J1_7-Pad3)") (class "Default")
      (node (ref "J1_7") (pin "3") (pinfunction "3_3") (pintype "passive"))
    )
    (net (code "47") (name "unconnected-(J1_9-Pad1)") (class "Default")
      (node (ref "J1_9") (pin "1") (pinfunction "1_1") (pintype "passive+no_connect"))
    )
    (net (code "48") (name "unconnected-(J1_9-Pad3)") (class "Default")
      (node (ref "J1_9") (pin "3") (pinfunction "3_3") (pintype "passive+no_connect"))
    )
    (net (code "49") (name "unconnected-(J1_9-Pad5)") (class "Default")
      (node (ref "J1_9") (pin "5") (pinfunction "5_5") (pintype "passive+no_connect"))
    )
    (net (code "50") (name "unconnected-(J1_9-Pad7)") (class "Default")
      (node (ref "J1_9") (pin "7") (pinfunction "7_7") (pintype "passive+no_connect"))
    )
    (net (code "51") (name "unconnected-(J1_9-Pad9)") (class "Default")
      (node (ref "J1_9") (pin "9") (pinfunction "9_9") (pintype "passive+no_connect"))
    )
    (net (code "52") (name "unconnected-(J1_9-Pad10)") (class "Default")
      (node (ref "J1_9") (pin "10") (pinfunction "10_10") (pintype "passive+no_connect"))
    )
    (net (code "53") (name "unconnected-(U1_1-PA2-Pad19)") (class "Default")
      (node (ref "U1_1") (pin "19") (pinfunction "PA2_19") (pintype "passive+no_connect"))
    )
    (net (code "54") (name "unconnected-(U1_1-PA10-Pad27)") (class "Default")
      (node (ref "U1_1") (pin "27") (pinfunction "PA10_27") (pintype "passive+no_connect"))
    )
    (net (code "55") (name "unconnected-(U1_1-PB0-Pad28)") (class "Default")
      (node (ref "U1_1") (pin "28") (pinfunction "PB0_28") (pintype "passive+no_connect"))
    )
    (net (code "56") (name "unconnected-(U1_1-PB3-Pad8)") (class "Default")
      (node (ref "U1_1") (pin "8") (pinfunction "PB3_8") (pintype "passive+no_connect"))
    )
    (net (code "57") (name "unconnected-(U1_1-PB5-Pad11)") (class "Default")
      (node (ref "U1_1") (pin "11") (pinfunction "PB5_11") (pintype "passive+no_connect"))
    )
    (net (code "58") (name "unconnected-(U1_1-PB6-Pad10)") (class "Default")
      (node (ref "U1_1") (pin "10") (pinfunction "PB6_10") (pintype "passive+no_connect"))
    )
    (net (code "59") (name "unconnected-(U1_1-PB7-Pad9)") (class "Default")
      (node (ref "U1_1") (pin "9") (pinfunction "PB7_9") (pintype "passive+no_connect"))
    )
    (net (code "60") (name "unconnected-(U1_1-PB9-Pad25)") (class "Default")
      (node (ref "U1_1") (pin "25") (pinfunction "PB9_25") (pintype "passive+no_connect"))
    )
    (net (code "61") (name "unconnected-(U1_1-PB13-Pad24)") (class "Default")
      (node (ref "U1_1") (pin "24") (pinfunction "PB13_24") (pintype "passive+no_connect"))
    )
    (net (code "62") (name "unconnected-(U1_1-PB14-Pad26)") (class "Default")
      (node (ref "U1_1") (pin "26") (pinfunction "PB14_26") (pintype "passive+no_connect"))
    )
    (net (code "63") (name "unconnected-(U1_1-PC0-Pad13)") (class "Default")
      (node (ref "U1_1") (pin "13") (pinfunction "PC0_13") (pintype "passive+no_connect"))
    )
    (net (code "64") (name "unconnected-(U1_1-PC1-Pad12)") (class "Default")
      (node (ref "U1_1") (pin "12") (pinfunction "PC1_12") (pintype "passive+no_connect"))
    )
    (net (code "65") (name "unconnected-(U1_3-FTY-Pad5)") (class "Default")
      (node (ref "U1_3") (pin "5") (pinfunction "FTY_5") (pintype "passive+no_connect"))
    )
    (net (code "66") (name "unconnected-(U1_5-CC1-PadA5)") (class "Default")
      (node (ref "U1_5") (pin "A5") (pinfunction "CC1_A5") (pintype "passive+no_connect"))
    )
    (net (code "67") (name "unconnected-(U1_5-CC2-PadB5)") (class "Default")
      (node (ref "U1_5") (pin "B5") (pinfunction "CC2_B5") (pintype "passive+no_connect"))
    )
    (net (code "68") (name "unconnected-(U1_5-Dn1-PadA7)") (class "Default")
      (node (ref "U1_5") (pin "A7") (pinfunction "Dn1_A7") (pintype "passive+no_connect"))
    )
    (net (code "69") (name "unconnected-(U1_5-Dn2-PadB7)") (class "Default")
      (node (ref "U1_5") (pin "B7") (pinfunction "Dn2_B7") (pintype "passive+no_connect"))
    )
    (net (code "70") (name "unconnected-(U1_5-Dp1-PadA6)") (class "Default")
      (node (ref "U1_5") (pin "A6") (pinfunction "Dp1_A6") (pintype "passive+no_connect"))
    )
    (net (code "71") (name "unconnected-(U1_5-Dp2-PadB6)") (class "Default")
      (node (ref "U1_5") (pin "B6") (pinfunction "Dp2_B6") (pintype "passive+no_connect"))
    )
    (net (code "72") (name "unconnected-(U1_5-SBU1-PadA8)") (class "Default")
      (node (ref "U1_5") (pin "A8") (pinfunction "SBU1_A8") (pintype "passive+no_connect"))
    )
    (net (code "73") (name "unconnected-(U1_5-SBU2-PadB8)") (class "Default")
      (node (ref "U1_5") (pin "B8") (pinfunction "SBU2_B8") (pintype "passive+no_connect"))
    )
    (net (code "74") (name "unconnected-(U1_5-SSRXn1-PadB10)") (class "Default")
      (node (ref "U1_5") (pin "B10") (pinfunction "SSRXn1_B10") (pintype "passive+no_connect"))
    )
    (net (code "75") (name "unconnected-(U1_5-SSRXn2-PadA10)") (class "Default")
      (node (ref "U1_5") (pin "A10") (pinfunction "SSRXn2_A10") (pintype "passive+no_connect"))
    )
    (net (code "76") (name "unconnected-(U1_5-SSRXp1-PadB11)") (class "Default")
      (node (ref "U1_5") (pin "B11") (pinfunction "SSRXp1_B11") (pintype "passive+no_connect"))
    )
    (net (code "77") (name "unconnected-(U1_5-SSRXp2-PadA11)") (class "Default")
      (node (ref "U1_5") (pin "A11") (pinfunction "SSRXp2_A11") (pintype "passive+no_connect"))
    )
    (net (code "78") (name "unconnected-(U1_5-SSTXn1-PadA3)") (class "Default")
      (node (ref "U1_5") (pin "A3") (pinfunction "SSTXn1_A3") (pintype "passive+no_connect"))
    )
    (net (code "79") (name "unconnected-(U1_5-SSTXn2-PadB3)") (class "Default")
      (node (ref "U1_5") (pin "B3") (pinfunction "SSTXn2_B3") (pintype "passive+no_connect"))
    )
    (net (code "80") (name "unconnected-(U1_5-SSTXp1-PadA2)") (class "Default")
      (node (ref "U1_5") (pin "A2") (pinfunction "SSTXp1_A2") (pintype "passive+no_connect"))
    )
    (net (code "81") (name "unconnected-(U1_5-SSTXp2-PadB2)") (class "Default")
      (node (ref "U1_5") (pin "B2") (pinfunction "SSTXp2_B2") (pintype "passive+no_connect"))
    )
    (net (code "82") (name "unconnected-(U1_6-PIO-Pad8)") (class "Default")
      (node (ref "U1_6") (pin "8") (pinfunction "PIO_8") (pintype "input+no_connect"))
    )
    (net (code "83") (name "unconnected-(U1_7-*PG-Pad7)") (class "Default")
      (node (ref "U1_7") (pin "7") (pinfunction "*PG_7") (pintype "input+no_connect"))
    )
    (net (code "84") (name "unconnected-(U1_7-STAT1-Pad3)") (class "Default")
      (node (ref "U1_7") (pin "3") (pinfunction "STAT1_3") (pintype "output+no_connect"))
    )
    (net (code "85") (name "unconnected-(U1_7-STAT2-Pad4)") (class "Default")
      (node (ref "U1_7") (pin "4") (pinfunction "STAT2_4") (pintype "output+no_connect"))
    )
    (net (code "86") (name "unconnected-(U1_7-THERM-Pad8)") (class "Default")
      (node (ref "U1_7") (pin "8") (pinfunction "THERM_8") (pintype "input+no_connect"))
    )
    (net (code "87") (name "unconnected-(U1_7-VBAT_2-Pad9)") (class "Default")
      (node (ref "U1_7") (pin "9") (pinfunction "VBAT_2_9") (pintype "output+no_connect"))
    )
    (net (code "88") (name "unconnected-(U1_8-XSHUT-Pad8)") (class "Default")
      (node (ref "U1_8") (pin "8") (pinfunction "XSHUT_8") (pintype "input+no_connect"))
    )
  )
)
